# calip2.net
KiCad netlist of a schematic drawn in EAGLE
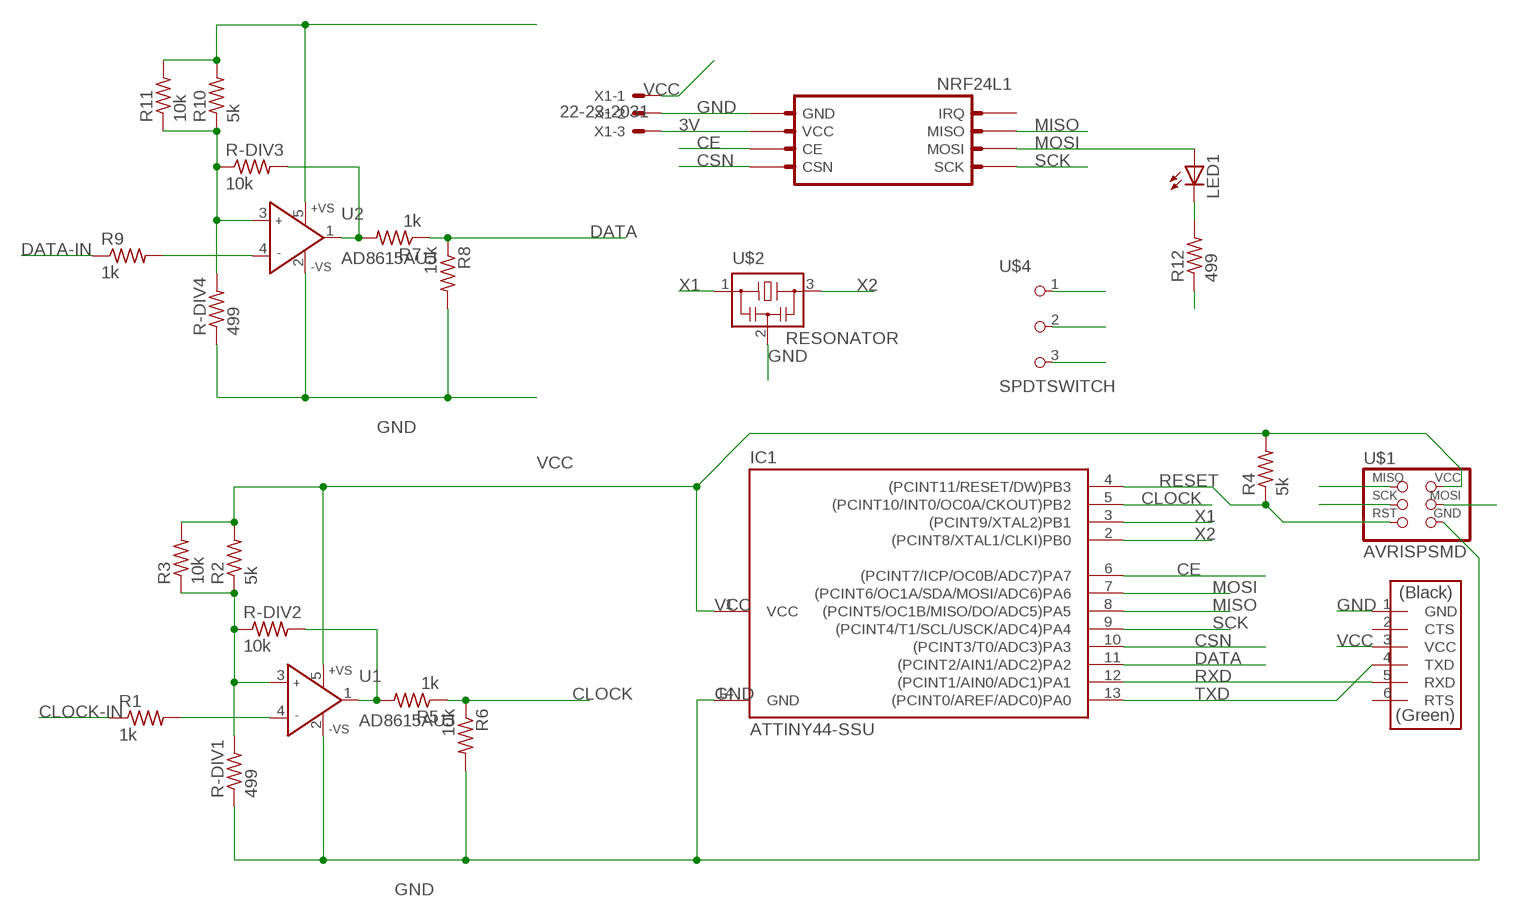
[diagram p0: schematic, sheet 1]

(export (version "E")
  (design (tool "Eeschema 10.0.6"))
  (components
    (comp (ref "IC1")
      (value "ATTINY44-SSU")
      (footprint "eagle-import:SOIC14")
      (libsource (lib "eagle-import") (part "ATTINY44-SSU"))
    )
    (comp (ref "LED1")
      (value "LEDSML1206")
      (footprint "eagle-import:SML1206")
      (libsource (lib "eagle-import") (part "LEDSML1206"))
    )
    (comp (ref "NRF24L1")
      (value "NRF")
      (footprint "eagle-import:NRF")
      (libsource (lib "eagle-import") (part "NRF"))
    )
    (comp (ref "R-DIV1")
      (value "499")
      (footprint "eagle-import:R1206FAB")
      (libsource (lib "eagle-import") (part "RES-US1206FAB"))
    )
    (comp (ref "R-DIV2")
      (value "10k")
      (footprint "eagle-import:R1206FAB")
      (libsource (lib "eagle-import") (part "RES-US1206FAB"))
    )
    (comp (ref "R-DIV3")
      (value "10k")
      (footprint "eagle-import:R1206FAB")
      (libsource (lib "eagle-import") (part "RES-US1206FAB"))
    )
    (comp (ref "R-DIV4")
      (value "499")
      (footprint "eagle-import:R1206FAB")
      (libsource (lib "eagle-import") (part "RES-US1206FAB"))
    )
    (comp (ref "R1")
      (value "1k")
      (footprint "eagle-import:R1206FAB")
      (libsource (lib "eagle-import") (part "RES-US1206FAB"))
    )
    (comp (ref "R2")
      (value "5k")
      (footprint "eagle-import:R1206FAB")
      (libsource (lib "eagle-import") (part "RES-US1206FAB"))
    )
    (comp (ref "R3")
      (value "10k")
      (footprint "eagle-import:R1206FAB")
      (libsource (lib "eagle-import") (part "RES-US1206FAB"))
    )
    (comp (ref "R4")
      (value "5k")
      (footprint "eagle-import:R1206FAB")
      (libsource (lib "eagle-import") (part "RES-US1206FAB"))
    )
    (comp (ref "R5")
      (value "1k")
      (footprint "eagle-import:R1206FAB")
      (libsource (lib "eagle-import") (part "RES-US1206FAB"))
    )
    (comp (ref "R6")
      (value "10k")
      (footprint "eagle-import:R1206FAB")
      (libsource (lib "eagle-import") (part "RES-US1206FAB"))
    )
    (comp (ref "R7")
      (value "1k")
      (footprint "eagle-import:R1206FAB")
      (libsource (lib "eagle-import") (part "RES-US1206FAB"))
    )
    (comp (ref "R8")
      (value "10k")
      (footprint "eagle-import:R1206FAB")
      (libsource (lib "eagle-import") (part "RES-US1206FAB"))
    )
    (comp (ref "R9")
      (value "1k")
      (footprint "eagle-import:R1206FAB")
      (libsource (lib "eagle-import") (part "RES-US1206FAB"))
    )
    (comp (ref "R10")
      (value "5k")
      (footprint "eagle-import:R1206FAB")
      (libsource (lib "eagle-import") (part "RES-US1206FAB"))
    )
    (comp (ref "R11")
      (value "10k")
      (footprint "eagle-import:R1206FAB")
      (libsource (lib "eagle-import") (part "RES-US1206FAB"))
    )
    (comp (ref "R12")
      (value "499")
      (footprint "eagle-import:R1206FAB")
      (libsource (lib "eagle-import") (part "RES-US1206FAB"))
    )
    (comp (ref "U$1")
      (value "AVRISPSMD")
      (footprint "eagle-import:2X03SMD")
      (libsource (lib "eagle-import") (part "AVRISPSMD"))
    )
    (comp (ref "U$2")
      (value "RESONATOR")
      (footprint "eagle-import:EFOBM")
      (libsource (lib "eagle-import") (part "RESONATOR"))
    )
    (comp (ref "U$3")
      (value "FTDI-SMD-HEADER")
      (footprint "eagle-import:1X06SMD")
      (libsource (lib "eagle-import") (part "FTDI-SMD-HEADER"))
    )
    (comp (ref "U$4")
      (value "SPDTSWITCH")
      (footprint "eagle-import:SPDTSWITCH")
      (libsource (lib "eagle-import") (part "SPDTSWITCH"))
    )
    (comp (ref "U1")
      (value "AD8615AUJ")
      (footprint "eagle-import:TSOT23-5")
      (libsource (lib "eagle-import") (part "AD8615UJA"))
    )
    (comp (ref "U2")
      (value "AD8615AUJ")
      (footprint "eagle-import:TSOT23-5")
      (libsource (lib "eagle-import") (part "AD8615UJA"))
    )
    (comp (ref "X1")
      (value "22-23-2031")
      (footprint "eagle-import:22-23-2031")
      (fields (field (name "MF") "MOLEX"))
      (libsource (lib "eagle-import") (part "22-23-2031"))
    )
  )
  (nets
    (net (code "1") (name "/3V") (class "Default")
      (node (ref "NRF24L1") (pin "2") (pinfunction "VCC_2") (pintype "power_in"))
      (node (ref "X1") (pin "3") (pinfunction "S_3") (pintype "passive"))
    )
    (net (code "2") (name "/CE") (class "Default")
      (node (ref "IC1") (pin "6") (pinfunction "(PCINT7/ICP/OC0B/ADC7)PA7_6") (pintype "bidirectional"))
      (node (ref "NRF24L1") (pin "3") (pinfunction "CE_3") (pintype "bidirectional"))
    )
    (net (code "3") (name "/CLOCK") (class "Default")
      (node (ref "IC1") (pin "5") (pinfunction "(PCINT10/INT0/OC0A/CKOUT)PB2_5") (pintype "bidirectional"))
      (node (ref "R5") (pin "1") (pinfunction "1_1") (pintype "passive"))
      (node (ref "R6") (pin "1") (pinfunction "1_1") (pintype "passive"))
    )
    (net (code "4") (name "/CLOCK-IN") (class "Default")
      (node (ref "R1") (pin "1") (pinfunction "1_1") (pintype "passive"))
      (node (ref "U$4") (pin "2") (pinfunction "2_2") (pintype "passive"))
    )
    (net (code "5") (name "/CSN") (class "Default")
      (node (ref "IC1") (pin "10") (pinfunction "(PCINT3/T0/ADC3)PA3_10") (pintype "bidirectional"))
      (node (ref "NRF24L1") (pin "4") (pinfunction "CSN_4") (pintype "bidirectional"))
    )
    (net (code "6") (name "/DATA") (class "Default")
      (node (ref "IC1") (pin "11") (pinfunction "(PCINT2/AIN1/ADC2)PA2_11") (pintype "bidirectional"))
      (node (ref "R7") (pin "1") (pinfunction "1_1") (pintype "passive"))
      (node (ref "R8") (pin "1") (pinfunction "1_1") (pintype "passive"))
    )
    (net (code "7") (name "/DATA-IN") (class "Default")
      (node (ref "R9") (pin "1") (pinfunction "1_1") (pintype "passive"))
      (node (ref "U$4") (pin "3") (pinfunction "3_3") (pintype "passive"))
    )
    (net (code "8") (name "/GND") (class "Default")
      (node (ref "IC1") (pin "14") (pinfunction "GND_14") (pintype "power_in"))
      (node (ref "NRF24L1") (pin "P$1") (pinfunction "GND_P$1") (pintype "power_in"))
      (node (ref "R-DIV1") (pin "1") (pinfunction "1_1") (pintype "passive"))
      (node (ref "R-DIV4") (pin "1") (pinfunction "1_1") (pintype "passive"))
      (node (ref "R12") (pin "1") (pinfunction "1_1") (pintype "passive"))
      (node (ref "R6") (pin "2") (pinfunction "2_2") (pintype "passive"))
      (node (ref "R8") (pin "2") (pinfunction "2_2") (pintype "passive"))
      (node (ref "U$1") (pin "6") (pinfunction "GND_6") (pintype "passive"))
      (node (ref "U$2") (pin "2") (pinfunction "2_2") (pintype "passive"))
      (node (ref "U$3") (pin "1") (pinfunction "GND_1") (pintype "bidirectional"))
      (node (ref "U$4") (pin "1") (pinfunction "1_1") (pintype "passive"))
      (node (ref "U1") (pin "2") (pinfunction "-VS_2") (pintype "input"))
      (node (ref "U2") (pin "2") (pinfunction "-VS_2") (pintype "input"))
      (node (ref "X1") (pin "2") (pinfunction "S_2") (pintype "passive"))
    )
    (net (code "9") (name "/MISO") (class "Default")
      (node (ref "IC1") (pin "8") (pinfunction "(PCINT5/OC1B/MISO/DO/ADC5)PA5_8") (pintype "bidirectional"))
      (node (ref "NRF24L1") (pin "7") (pinfunction "MISO_7") (pintype "bidirectional"))
      (node (ref "U$1") (pin "1") (pinfunction "MISO_1") (pintype "passive"))
    )
    (net (code "10") (name "/MOSI") (class "Default")
      (node (ref "IC1") (pin "7") (pinfunction "(PCINT6/OC1A/SDA/MOSI/ADC6)PA6_7") (pintype "bidirectional"))
      (node (ref "LED1") (pin "A") (pinfunction "A_A") (pintype "passive"))
      (node (ref "NRF24L1") (pin "6") (pinfunction "MOSI_6") (pintype "bidirectional"))
      (node (ref "U$1") (pin "4") (pinfunction "MOSI_4") (pintype "passive"))
    )
    (net (code "11") (name "/RESET") (class "Default")
      (node (ref "IC1") (pin "4") (pinfunction "(PCINT11/RESET/DW)PB3_4") (pintype "bidirectional"))
      (node (ref "R4") (pin "1") (pinfunction "1_1") (pintype "passive"))
      (node (ref "U$1") (pin "5") (pinfunction "RST_5") (pintype "passive"))
    )
    (net (code "12") (name "/RXD") (class "Default")
      (node (ref "IC1") (pin "12") (pinfunction "(PCINT1/AIN0/ADC1)PA1_12") (pintype "bidirectional"))
      (node (ref "U$3") (pin "5") (pinfunction "RXD_5") (pintype "bidirectional"))
    )
    (net (code "13") (name "/SCK") (class "Default")
      (node (ref "IC1") (pin "9") (pinfunction "(PCINT4/T1/SCL/USCK/ADC4)PA4_9") (pintype "bidirectional"))
      (node (ref "NRF24L1") (pin "5") (pinfunction "SCK_5") (pintype "bidirectional"))
      (node (ref "U$1") (pin "3") (pinfunction "SCK_3") (pintype "passive"))
    )
    (net (code "14") (name "/TXD") (class "Default")
      (node (ref "IC1") (pin "13") (pinfunction "(PCINT0/AREF/ADC0)PA0_13") (pintype "bidirectional"))
      (node (ref "U$3") (pin "4") (pinfunction "TXD_4") (pintype "bidirectional"))
    )
    (net (code "15") (name "/VCC") (class "Default")
      (node (ref "IC1") (pin "1") (pinfunction "VCC_1") (pintype "power_in"))
      (node (ref "R10") (pin "2") (pinfunction "2_2") (pintype "passive"))
      (node (ref "R11") (pin "2") (pinfunction "2_2") (pintype "passive"))
      (node (ref "R2") (pin "2") (pinfunction "2_2") (pintype "passive"))
      (node (ref "R3") (pin "2") (pinfunction "2_2") (pintype "passive"))
      (node (ref "R4") (pin "2") (pinfunction "2_2") (pintype "passive"))
      (node (ref "U$1") (pin "2") (pinfunction "VCC_2") (pintype "passive"))
      (node (ref "U$3") (pin "3") (pinfunction "VCC_3") (pintype "bidirectional"))
      (node (ref "U1") (pin "5") (pinfunction "+VS_5") (pintype "input"))
      (node (ref "U2") (pin "5") (pinfunction "+VS_5") (pintype "input"))
      (node (ref "X1") (pin "1") (pinfunction "S_1") (pintype "passive"))
    )
    (net (code "16") (name "/X1") (class "Default")
      (node (ref "IC1") (pin "3") (pinfunction "(PCINT9/XTAL2)PB1_3") (pintype "bidirectional"))
      (node (ref "U$2") (pin "1") (pinfunction "1_1") (pintype "passive"))
    )
    (net (code "17") (name "/X2") (class "Default")
      (node (ref "IC1") (pin "2") (pinfunction "(PCINT8/XTAL1/CLKI)PB0_2") (pintype "bidirectional"))
      (node (ref "U$2") (pin "3") (pinfunction "3_3") (pintype "passive"))
    )
    (net (code "18") (name "Net-(LED1-PadC)") (class "Default")
      (node (ref "LED1") (pin "C") (pinfunction "C_C") (pintype "passive"))
      (node (ref "R12") (pin "2") (pinfunction "2_2") (pintype "passive"))
    )
    (net (code "19") (name "Net-(U1-IN+)") (class "Default")
      (node (ref "R-DIV1") (pin "2") (pinfunction "2_2") (pintype "passive"))
      (node (ref "R-DIV2") (pin "1") (pinfunction "1_1") (pintype "passive"))
      (node (ref "R2") (pin "1") (pinfunction "1_1") (pintype "passive"))
      (node (ref "R3") (pin "1") (pinfunction "1_1") (pintype "passive"))
      (node (ref "U1") (pin "3") (pinfunction "IN+_3") (pintype "input"))
    )
    (net (code "20") (name "Net-(U1-IN-)") (class "Default")
      (node (ref "R1") (pin "2") (pinfunction "2_2") (pintype "passive"))
      (node (ref "U1") (pin "4") (pinfunction "IN-_4") (pintype "input"))
    )
    (net (code "21") (name "Net-(U1-OUT)") (class "Default")
      (node (ref "R-DIV2") (pin "2") (pinfunction "2_2") (pintype "passive"))
      (node (ref "R5") (pin "2") (pinfunction "2_2") (pintype "passive"))
      (node (ref "U1") (pin "1") (pinfunction "OUT_1") (pintype "output"))
    )
    (net (code "22") (name "Net-(U2-IN+)") (class "Default")
      (node (ref "R-DIV3") (pin "1") (pinfunction "1_1") (pintype "passive"))
      (node (ref "R-DIV4") (pin "2") (pinfunction "2_2") (pintype "passive"))
      (node (ref "R10") (pin "1") (pinfunction "1_1") (pintype "passive"))
      (node (ref "R11") (pin "1") (pinfunction "1_1") (pintype "passive"))
      (node (ref "U2") (pin "3") (pinfunction "IN+_3") (pintype "input"))
    )
    (net (code "23") (name "Net-(U2-IN-)") (class "Default")
      (node (ref "R9") (pin "2") (pinfunction "2_2") (pintype "passive"))
      (node (ref "U2") (pin "4") (pinfunction "IN-_4") (pintype "input"))
    )
    (net (code "24") (name "Net-(U2-OUT)") (class "Default")
      (node (ref "R-DIV3") (pin "2") (pinfunction "2_2") (pintype "passive"))
      (node (ref "R7") (pin "2") (pinfunction "2_2") (pintype "passive"))
      (node (ref "U2") (pin "1") (pinfunction "OUT_1") (pintype "output"))
    )
    (net (code "25") (name "unconnected-(NRF24L1-IRQ-Pad8)") (class "Default")
      (node (ref "NRF24L1") (pin "8") (pinfunction "IRQ_8") (pintype "bidirectional"))
    )
    (net (code "26") (name "unconnected-(U$3-CTS-Pad2)") (class "Default")
      (node (ref "U$3") (pin "2") (pinfunction "CTS_2") (pintype "bidirectional"))
    )
    (net (code "27") (name "unconnected-(U$3-RTS-Pad6)") (class "Default")
      (node (ref "U$3") (pin "6") (pinfunction "RTS_6") (pintype "bidirectional"))
    )
  )
)
